# growth_v2.net
KiCad netlist of a schematic drawn in EAGLE
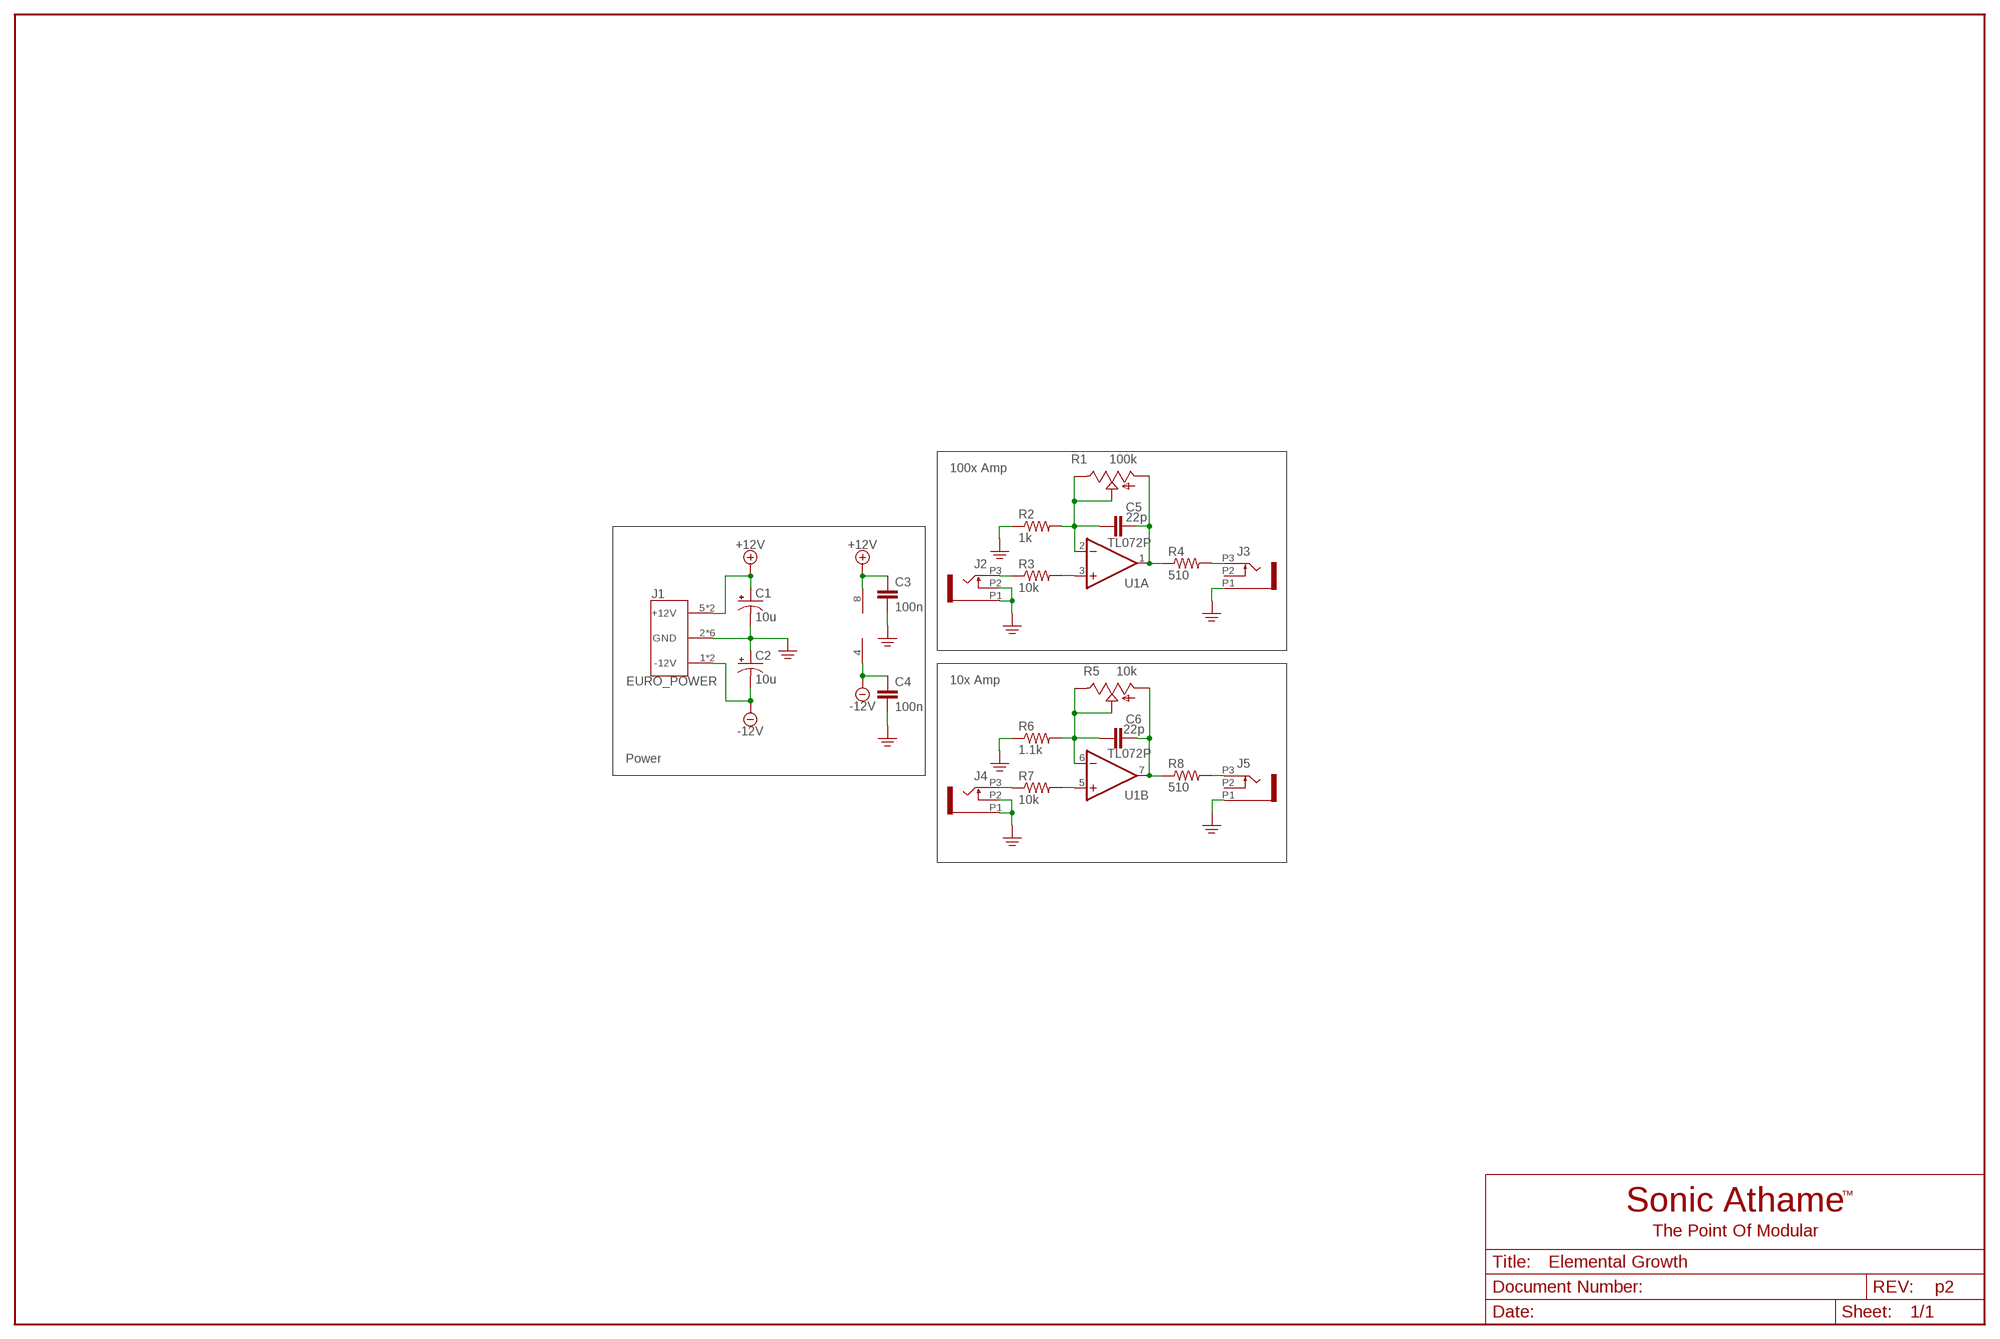
[diagram p0: schematic, sheet 1]

(export (version "E")
  (design (tool "Eeschema 10.0.6"))
  (components
    (comp (ref "C1")
      (value "10u")
      (footprint "eagle-import:TT2D5L_FLIP")
      (libsource (lib "eagle-import") (part "CAP_POLLYTIC_H_L"))
    )
    (comp (ref "C2")
      (value "10u")
      (footprint "eagle-import:TT2D5L_FLIP")
      (libsource (lib "eagle-import") (part "CAP_POLLYTIC_H_L"))
    )
    (comp (ref "C3")
      (value "100n")
      (footprint "eagle-import:C025-024X044")
      (libsource (lib "eagle-import") (part "CAP_NONPOL025-024X044"))
    )
    (comp (ref "C4")
      (value "100n")
      (footprint "eagle-import:C025-024X044")
      (libsource (lib "eagle-import") (part "CAP_NONPOL025-024X044"))
    )
    (comp (ref "C5")
      (value "22p")
      (footprint "eagle-import:C050-024X044")
      (libsource (lib "eagle-import") (part "CAP_NONPOL050-024X044"))
    )
    (comp (ref "C6")
      (value "22p")
      (footprint "eagle-import:C050-024X044")
      (libsource (lib "eagle-import") (part "CAP_NONPOL050-024X044"))
    )
    (comp (ref "J1")
      (value "EURO_POWER")
      (footprint "eagle-import:EURO_POWER")
      (libsource (lib "eagle-import") (part "EURO_POWER"))
    )
    (comp (ref "J2")
      (value "WQP-PJ398SM6")
      (footprint "eagle-import:WQP_PJ_301M6")
      (libsource (lib "eagle-import") (part "WQP-PJ398SM6"))
    )
    (comp (ref "J3")
      (value "WQP-PJ398SM6")
      (footprint "eagle-import:WQP_PJ_301M6")
      (libsource (lib "eagle-import") (part "WQP-PJ398SM6"))
    )
    (comp (ref "J4")
      (value "WQP-PJ398SM6")
      (footprint "eagle-import:WQP_PJ_301M6")
      (libsource (lib "eagle-import") (part "WQP-PJ398SM6"))
    )
    (comp (ref "J5")
      (value "WQP-PJ398SM6")
      (footprint "eagle-import:WQP_PJ_301M6")
      (libsource (lib "eagle-import") (part "WQP-PJ398SM6"))
    )
    (comp (ref "R1")
      (value "100k")
      (footprint "eagle-import:ALPHA_POT_VERTICAL")
      (libsource (lib "eagle-import") (part "ALPHA_POT_VERTICALVERTICAL"))
    )
    (comp (ref "R2")
      (value "1k")
      (footprint "eagle-import:0207_2V")
      (libsource (lib "eagle-import") (part "RESISTOR0207/2V"))
    )
    (comp (ref "R3")
      (value "10k")
      (footprint "eagle-import:0207_2V")
      (libsource (lib "eagle-import") (part "RESISTOR0207/2V"))
    )
    (comp (ref "R4")
      (value "510")
      (footprint "eagle-import:0207_2V")
      (libsource (lib "eagle-import") (part "RESISTOR0207/2V"))
    )
    (comp (ref "R5")
      (value "10k")
      (footprint "eagle-import:ALPHA_POT_VERTICAL")
      (libsource (lib "eagle-import") (part "ALPHA_POT_VERTICALVERTICAL"))
    )
    (comp (ref "R6")
      (value "1.1k")
      (footprint "eagle-import:0207_2V")
      (libsource (lib "eagle-import") (part "RESISTOR0207/2V"))
    )
    (comp (ref "R7")
      (value "10k")
      (footprint "eagle-import:0207_2V")
      (libsource (lib "eagle-import") (part "RESISTOR0207/2V"))
    )
    (comp (ref "R8")
      (value "510")
      (footprint "eagle-import:0207_2V")
      (libsource (lib "eagle-import") (part "RESISTOR0207/2V"))
    )
    (comp (ref "U1")
      (value "TL072P")
      (footprint "eagle-import:DIL08")
      (libsource (lib "eagle-import") (part "TL072P"))
    )
  )
  (nets
    (net (code "1") (name "+12V") (class "Default")
      (node (ref "C1") (pin "+") (pinfunction "+_+") (pintype "passive"))
      (node (ref "C3") (pin "1") (pinfunction "1_1") (pintype "passive"))
      (node (ref "J1") (pin "5") (pinfunction "+12V_5") (pintype "bidirectional"))
      (node (ref "J1") (pin "6") (pinfunction "+12V_6") (pintype "bidirectional"))
      (node (ref "U1") (pin "8") (pinfunction "V+_8") (pintype "power_in"))
    )
    (net (code "2") (name "-12V") (class "Default")
      (node (ref "C2") (pin "-") (pinfunction "-_-") (pintype "passive"))
      (node (ref "C4") (pin "1") (pinfunction "1_1") (pintype "passive"))
      (node (ref "J1") (pin "1") (pinfunction "-12V_1") (pintype "bidirectional"))
      (node (ref "J1") (pin "10") (pinfunction "-12V_10") (pintype "bidirectional"))
      (node (ref "U1") (pin "4") (pinfunction "V-_4") (pintype "power_in"))
    )
    (net (code "3") (name "GND") (class "Default")
      (node (ref "C1") (pin "-") (pinfunction "-_-") (pintype "passive"))
      (node (ref "C2") (pin "+") (pinfunction "+_+") (pintype "passive"))
      (node (ref "C3") (pin "2") (pinfunction "2_2") (pintype "passive"))
      (node (ref "C4") (pin "2") (pinfunction "2_2") (pintype "passive"))
      (node (ref "J1") (pin "2") (pinfunction "GND_2") (pintype "bidirectional"))
      (node (ref "J1") (pin "3") (pinfunction "GND_3") (pintype "bidirectional"))
      (node (ref "J1") (pin "4") (pinfunction "GND_4") (pintype "bidirectional"))
      (node (ref "J1") (pin "7") (pinfunction "GND_7") (pintype "bidirectional"))
      (node (ref "J1") (pin "8") (pinfunction "GND_8") (pintype "bidirectional"))
      (node (ref "J1") (pin "9") (pinfunction "GND_9") (pintype "bidirectional"))
      (node (ref "J2") (pin "P1") (pinfunction "1_P1") (pintype "passive"))
      (node (ref "J2") (pin "P2") (pinfunction "2_P2") (pintype "passive"))
      (node (ref "J3") (pin "P1") (pinfunction "1_P1") (pintype "passive"))
      (node (ref "J4") (pin "P1") (pinfunction "1_P1") (pintype "passive"))
      (node (ref "J4") (pin "P2") (pinfunction "2_P2") (pintype "passive"))
      (node (ref "J5") (pin "P1") (pinfunction "1_P1") (pintype "passive"))
      (node (ref "R2") (pin "1") (pinfunction "1_1") (pintype "passive"))
      (node (ref "R6") (pin "1") (pinfunction "1_1") (pintype "passive"))
    )
    (net (code "4") (name "Net-(J2-3)") (class "Default")
      (node (ref "J2") (pin "P3") (pinfunction "3_P3") (pintype "passive"))
      (node (ref "R3") (pin "1") (pinfunction "1_1") (pintype "passive"))
    )
    (net (code "5") (name "Net-(J3-3)") (class "Default")
      (node (ref "J3") (pin "P3") (pinfunction "3_P3") (pintype "passive"))
      (node (ref "R4") (pin "2") (pinfunction "2_2") (pintype "passive"))
    )
    (net (code "6") (name "Net-(J4-3)") (class "Default")
      (node (ref "J4") (pin "P3") (pinfunction "3_P3") (pintype "passive"))
      (node (ref "R7") (pin "1") (pinfunction "1_1") (pintype "passive"))
    )
    (net (code "7") (name "Net-(J5-3)") (class "Default")
      (node (ref "J5") (pin "P3") (pinfunction "3_P3") (pintype "passive"))
      (node (ref "R8") (pin "2") (pinfunction "2_2") (pintype "passive"))
    )
    (net (code "8") (name "Net-(R1-A)") (class "Default")
      (node (ref "C5") (pin "2") (pinfunction "2_2") (pintype "passive"))
      (node (ref "R1") (pin "P$3") (pinfunction "A_P$3") (pintype "passive"))
      (node (ref "R4") (pin "1") (pinfunction "1_1") (pintype "passive"))
      (node (ref "U1") (pin "1") (pinfunction "OUT_1") (pintype "output"))
    )
    (net (code "9") (name "Net-(R1-E)") (class "Default")
      (node (ref "C5") (pin "1") (pinfunction "1_1") (pintype "passive"))
      (node (ref "R1") (pin "P$1") (pinfunction "E_P$1") (pintype "passive"))
      (node (ref "R1") (pin "P$2") (pinfunction "S_P$2") (pintype "passive"))
      (node (ref "R2") (pin "2") (pinfunction "2_2") (pintype "passive"))
      (node (ref "U1") (pin "2") (pinfunction "-IN_2") (pintype "input"))
    )
    (net (code "10") (name "Net-(R5-A)") (class "Default")
      (node (ref "C6") (pin "2") (pinfunction "2_2") (pintype "passive"))
      (node (ref "R5") (pin "P$3") (pinfunction "A_P$3") (pintype "passive"))
      (node (ref "R8") (pin "1") (pinfunction "1_1") (pintype "passive"))
      (node (ref "U1") (pin "7") (pinfunction "OUT_7") (pintype "output"))
    )
    (net (code "11") (name "Net-(R5-E)") (class "Default")
      (node (ref "C6") (pin "1") (pinfunction "1_1") (pintype "passive"))
      (node (ref "R5") (pin "P$1") (pinfunction "E_P$1") (pintype "passive"))
      (node (ref "R5") (pin "P$2") (pinfunction "S_P$2") (pintype "passive"))
      (node (ref "R6") (pin "2") (pinfunction "2_2") (pintype "passive"))
      (node (ref "U1") (pin "6") (pinfunction "-IN_6") (pintype "input"))
    )
    (net (code "12") (name "Net-(U1A-+IN)") (class "Default")
      (node (ref "R3") (pin "2") (pinfunction "2_2") (pintype "passive"))
      (node (ref "U1") (pin "3") (pinfunction "+IN_3") (pintype "input"))
    )
    (net (code "13") (name "Net-(U1B-+IN)") (class "Default")
      (node (ref "R7") (pin "2") (pinfunction "2_2") (pintype "passive"))
      (node (ref "U1") (pin "5") (pinfunction "+IN_5") (pintype "input"))
    )
    (net (code "14") (name "unconnected-(J3-2-PadP2)") (class "Default")
      (node (ref "J3") (pin "P2") (pinfunction "2_P2") (pintype "passive"))
    )
    (net (code "15") (name "unconnected-(J5-2-PadP2)") (class "Default")
      (node (ref "J5") (pin "P2") (pinfunction "2_P2") (pintype "passive"))
    )
  )
)
